# Dover_Driver.net
KiCad netlist of a schematic drawn in EAGLE
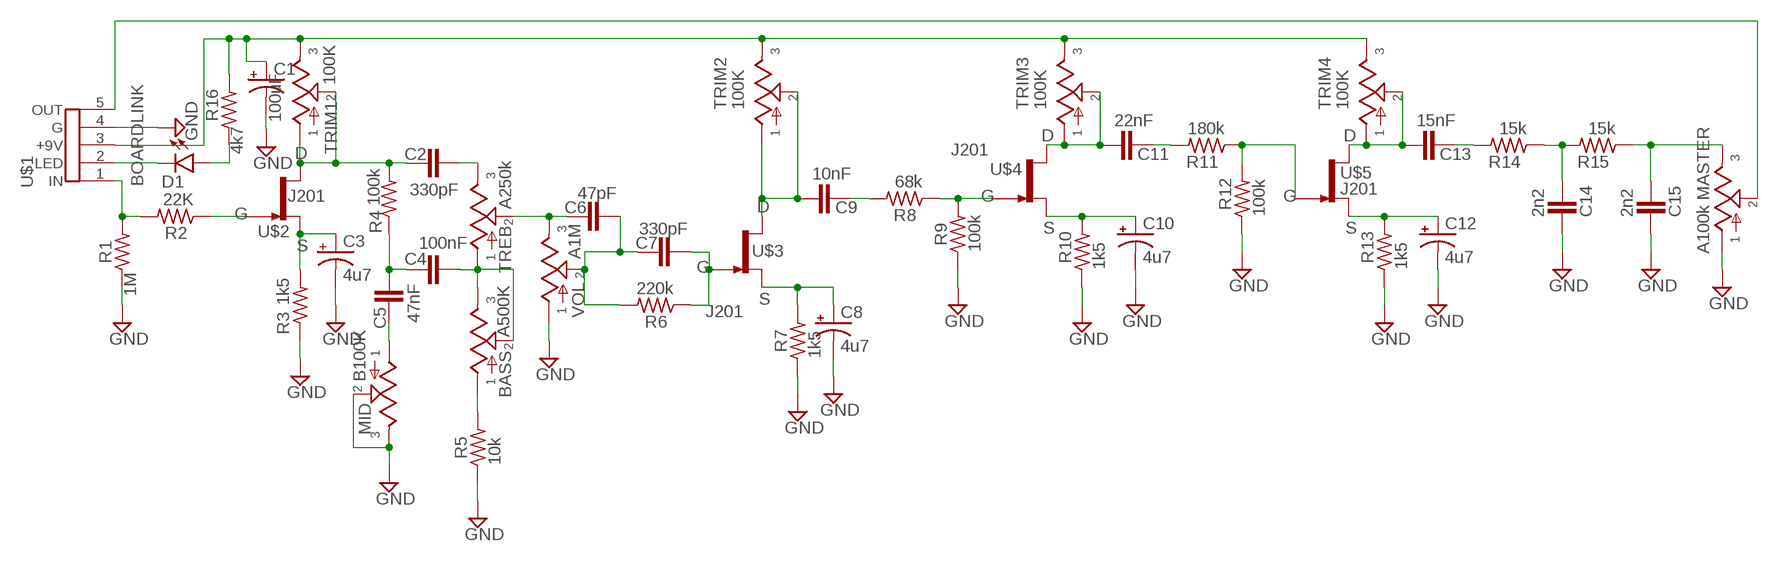
[diagram p0: schematic, sheet 1]

(export (version "E")
  (design (tool "Eeschema 10.0.6"))
  (components
    (comp (ref "BASS")
      (value "A500K")
      (footprint "eagle-import:16MM")
      (libsource (lib "eagle-import") (part "POT16MM"))
    )
    (comp (ref "C1")
      (value "100uF")
      (footprint "eagle-import:063_025")
      (libsource (lib "eagle-import") (part "0631"))
    )
    (comp (ref "C2")
      (value "330pF")
      (footprint "eagle-import:050X030_025")
      (libsource (lib "eagle-import") (part "050X030_0251"))
    )
    (comp (ref "C3")
      (value "4u7")
      (footprint "eagle-import:050_020_1")
      (libsource (lib "eagle-import") (part "0501"))
    )
    (comp (ref "C4")
      (value "100nF")
      (footprint "eagle-import:075X040")
      (libsource (lib "eagle-import") (part "075X0402"))
    )
    (comp (ref "C5")
      (value "47nF")
      (footprint "eagle-import:072X025")
      (libsource (lib "eagle-import") (part "072X0252"))
    )
    (comp (ref "C6")
      (value "47pF")
      (footprint "eagle-import:050X030_025")
      (libsource (lib "eagle-import") (part "050X030_0251"))
    )
    (comp (ref "C7")
      (value "330pF")
      (footprint "eagle-import:050X030_025")
      (libsource (lib "eagle-import") (part "050X030_0251"))
    )
    (comp (ref "C8")
      (value "4u7")
      (footprint "eagle-import:050_020_1")
      (libsource (lib "eagle-import") (part "0501"))
    )
    (comp (ref "C9")
      (value "10nF")
      (footprint "eagle-import:072X025")
      (libsource (lib "eagle-import") (part "072X0252"))
    )
    (comp (ref "C10")
      (value "4u7")
      (footprint "eagle-import:050_020_1")
      (libsource (lib "eagle-import") (part "0501"))
    )
    (comp (ref "C11")
      (value "22nF")
      (footprint "eagle-import:072X025")
      (libsource (lib "eagle-import") (part "072X0252"))
    )
    (comp (ref "C12")
      (value "4u7")
      (footprint "eagle-import:050_020_1")
      (libsource (lib "eagle-import") (part "0501"))
    )
    (comp (ref "C13")
      (value "15nF")
      (footprint "eagle-import:072X025")
      (libsource (lib "eagle-import") (part "072X0252"))
    )
    (comp (ref "C14")
      (value "2n2")
      (footprint "eagle-import:072X025")
      (libsource (lib "eagle-import") (part "072X0252"))
    )
    (comp (ref "C15")
      (value "2n2")
      (footprint "eagle-import:072X025")
      (libsource (lib "eagle-import") (part "072X0252"))
    )
    (comp (ref "D1")
      (value "LED3MM")
      (footprint "eagle-import:LED3MM")
      (libsource (lib "eagle-import") (part "LED3MM"))
    )
    (comp (ref "MASTER")
      (value "A100k")
      (footprint "eagle-import:16MM")
      (libsource (lib "eagle-import") (part "POT16MM"))
    )
    (comp (ref "MID")
      (value "B100K")
      (footprint "eagle-import:16MM")
      (libsource (lib "eagle-import") (part "POT16MM"))
    )
    (comp (ref "R1")
      (value "1M")
      (footprint "eagle-import:R0207_3")
      (libsource (lib "eagle-import") (part "6MM.3"))
    )
    (comp (ref "R2")
      (value "22K")
      (footprint "eagle-import:R0207_3")
      (libsource (lib "eagle-import") (part "6MM.3"))
    )
    (comp (ref "R3")
      (value "1k5")
      (footprint "eagle-import:R0207_3")
      (libsource (lib "eagle-import") (part "6MM.3"))
    )
    (comp (ref "R4")
      (value "100k")
      (footprint "eagle-import:R0207_3")
      (libsource (lib "eagle-import") (part "6MM.3"))
    )
    (comp (ref "R5")
      (value "10k")
      (footprint "eagle-import:R0207_3")
      (libsource (lib "eagle-import") (part "6MM.3"))
    )
    (comp (ref "R6")
      (value "220k")
      (footprint "eagle-import:R0207_3")
      (libsource (lib "eagle-import") (part "6MM.3"))
    )
    (comp (ref "R7")
      (value "1k5")
      (footprint "eagle-import:R0207_3")
      (libsource (lib "eagle-import") (part "6MM.3"))
    )
    (comp (ref "R8")
      (value "68k")
      (footprint "eagle-import:R0207_3")
      (libsource (lib "eagle-import") (part "6MM.3"))
    )
    (comp (ref "R9")
      (value "100k")
      (footprint "eagle-import:R0207_3")
      (libsource (lib "eagle-import") (part "6MM.3"))
    )
    (comp (ref "R10")
      (value "1k5")
      (footprint "eagle-import:R0207_3")
      (libsource (lib "eagle-import") (part "6MM.3"))
    )
    (comp (ref "R11")
      (value "180k")
      (footprint "eagle-import:R0207_3")
      (libsource (lib "eagle-import") (part "6MM.3"))
    )
    (comp (ref "R12")
      (value "100k")
      (footprint "eagle-import:R0207_3")
      (libsource (lib "eagle-import") (part "6MM.3"))
    )
    (comp (ref "R13")
      (value "1k5")
      (footprint "eagle-import:R0207_3")
      (libsource (lib "eagle-import") (part "6MM.3"))
    )
    (comp (ref "R14")
      (value "15k")
      (footprint "eagle-import:R0207_3")
      (libsource (lib "eagle-import") (part "6MM.3"))
    )
    (comp (ref "R15")
      (value "15k")
      (footprint "eagle-import:R0207_3")
      (libsource (lib "eagle-import") (part "6MM.3"))
    )
    (comp (ref "R16")
      (value "4k7")
      (footprint "eagle-import:R0207_3")
      (libsource (lib "eagle-import") (part "6MM.3"))
    )
    (comp (ref "TREB")
      (value "A250k")
      (footprint "eagle-import:16MM")
      (libsource (lib "eagle-import") (part "POT16MM"))
    )
    (comp (ref "TRIM1")
      (value "100K")
      (footprint "eagle-import:ROUNDTRIM")
      (libsource (lib "eagle-import") (part "xc_library_POTTRIM"))
    )
    (comp (ref "TRIM2")
      (value "100K")
      (footprint "eagle-import:ROUNDTRIM")
      (libsource (lib "eagle-import") (part "xc_library_POTTRIM"))
    )
    (comp (ref "TRIM3")
      (value "100K")
      (footprint "eagle-import:ROUNDTRIM")
      (libsource (lib "eagle-import") (part "xc_library_POTTRIM"))
    )
    (comp (ref "TRIM4")
      (value "100K")
      (footprint "eagle-import:ROUNDTRIM")
      (libsource (lib "eagle-import") (part "xc_library_POTTRIM"))
    )
    (comp (ref "U$1")
      (value "BOARDLINK")
      (footprint "eagle-import:BOARDLINK")
      (libsource (lib "eagle-import") (part "BOARDLINK"))
    )
    (comp (ref "U$2")
      (value "J201")
      (footprint "eagle-import:SOT23")
      (libsource (lib "eagle-import") (part "MMBF5458"))
    )
    (comp (ref "U$3")
      (value "J201")
      (footprint "eagle-import:SOT23")
      (libsource (lib "eagle-import") (part "MMBF5458"))
    )
    (comp (ref "U$4")
      (value "J201")
      (footprint "eagle-import:SOT23")
      (libsource (lib "eagle-import") (part "MMBF5458"))
    )
    (comp (ref "U$5")
      (value "J201")
      (footprint "eagle-import:SOT23")
      (libsource (lib "eagle-import") (part "MMBF5458"))
    )
    (comp (ref "VOL")
      (value "A1M")
      (footprint "eagle-import:16MM")
      (libsource (lib "eagle-import") (part "POT16MM"))
    )
  )
  (nets
    (net (code "1") (name "GND") (class "Default")
      (node (ref "C1") (pin "-") (pinfunction "-_-") (pintype "passive"))
      (node (ref "C10") (pin "-") (pinfunction "-_-") (pintype "passive"))
      (node (ref "C12") (pin "-") (pinfunction "-_-") (pintype "passive"))
      (node (ref "C14") (pin "2") (pinfunction "2_2") (pintype "passive"))
      (node (ref "C15") (pin "2") (pinfunction "2_2") (pintype "passive"))
      (node (ref "C3") (pin "-") (pinfunction "-_-") (pintype "passive"))
      (node (ref "C8") (pin "-") (pinfunction "-_-") (pintype "passive"))
      (node (ref "MASTER") (pin "1") (pinfunction "1_1") (pintype "passive"))
      (node (ref "MID") (pin "2") (pinfunction "2_2") (pintype "passive"))
      (node (ref "MID") (pin "3") (pinfunction "3_3") (pintype "passive"))
      (node (ref "R1") (pin "1") (pinfunction "1_1") (pintype "passive"))
      (node (ref "R10") (pin "1") (pinfunction "1_1") (pintype "passive"))
      (node (ref "R12") (pin "1") (pinfunction "1_1") (pintype "passive"))
      (node (ref "R13") (pin "1") (pinfunction "1_1") (pintype "passive"))
      (node (ref "R3") (pin "1") (pinfunction "1_1") (pintype "passive"))
      (node (ref "R5") (pin "1") (pinfunction "1_1") (pintype "passive"))
      (node (ref "R7") (pin "1") (pinfunction "1_1") (pintype "passive"))
      (node (ref "R9") (pin "1") (pinfunction "1_1") (pintype "passive"))
      (node (ref "U$1") (pin "4") (pinfunction "G_4") (pintype "bidirectional"))
      (node (ref "VOL") (pin "1") (pinfunction "1_1") (pintype "passive"))
    )
    (net (code "2") (name "Net-(BASS-Pad1)") (class "Default")
      (node (ref "BASS") (pin "1") (pinfunction "1_1") (pintype "passive"))
      (node (ref "R5") (pin "2") (pinfunction "2_2") (pintype "passive"))
    )
    (net (code "3") (name "Net-(BASS-Pad2)") (class "Default")
      (node (ref "BASS") (pin "2") (pinfunction "2_2") (pintype "passive"))
      (node (ref "BASS") (pin "3") (pinfunction "3_3") (pintype "passive"))
      (node (ref "C4") (pin "2") (pinfunction "2_2") (pintype "passive"))
      (node (ref "TREB") (pin "1") (pinfunction "1_1") (pintype "passive"))
    )
    (net (code "4") (name "Net-(C2-Pad2)") (class "Default")
      (node (ref "C2") (pin "2") (pinfunction "2_2") (pintype "passive"))
      (node (ref "TREB") (pin "3") (pinfunction "3_3") (pintype "passive"))
    )
    (net (code "5") (name "Net-(C4-Pad1)") (class "Default")
      (node (ref "C4") (pin "1") (pinfunction "1_1") (pintype "passive"))
      (node (ref "C5") (pin "2") (pinfunction "2_2") (pintype "passive"))
      (node (ref "R4") (pin "1") (pinfunction "1_1") (pintype "passive"))
    )
    (net (code "6") (name "Net-(C5-Pad1)") (class "Default")
      (node (ref "C5") (pin "1") (pinfunction "1_1") (pintype "passive"))
      (node (ref "MID") (pin "1") (pinfunction "1_1") (pintype "passive"))
    )
    (net (code "7") (name "Net-(C6-Pad1)") (class "Default")
      (node (ref "C6") (pin "1") (pinfunction "1_1") (pintype "passive"))
      (node (ref "TREB") (pin "2") (pinfunction "2_2") (pintype "passive"))
      (node (ref "VOL") (pin "3") (pinfunction "3_3") (pintype "passive"))
    )
    (net (code "8") (name "Net-(C6-Pad2)") (class "Default")
      (node (ref "C6") (pin "2") (pinfunction "2_2") (pintype "passive"))
      (node (ref "C7") (pin "1") (pinfunction "1_1") (pintype "passive"))
      (node (ref "R6") (pin "2") (pinfunction "2_2") (pintype "passive"))
      (node (ref "VOL") (pin "2") (pinfunction "2_2") (pintype "passive"))
    )
    (net (code "9") (name "Net-(C9-Pad1)") (class "Default")
      (node (ref "C9") (pin "1") (pinfunction "1_1") (pintype "passive"))
      (node (ref "R8") (pin "2") (pinfunction "2_2") (pintype "passive"))
    )
    (net (code "10") (name "Net-(C11-Pad1)") (class "Default")
      (node (ref "C11") (pin "1") (pinfunction "1_1") (pintype "passive"))
      (node (ref "R11") (pin "2") (pinfunction "2_2") (pintype "passive"))
    )
    (net (code "11") (name "Net-(C13-Pad1)") (class "Default")
      (node (ref "C13") (pin "1") (pinfunction "1_1") (pintype "passive"))
      (node (ref "R14") (pin "2") (pinfunction "2_2") (pintype "passive"))
    )
    (net (code "12") (name "Net-(C14-Pad1)") (class "Default")
      (node (ref "C14") (pin "1") (pinfunction "1_1") (pintype "passive"))
      (node (ref "R14") (pin "1") (pinfunction "1_1") (pintype "passive"))
      (node (ref "R15") (pin "2") (pinfunction "2_2") (pintype "passive"))
    )
    (net (code "13") (name "Net-(C15-Pad1)") (class "Default")
      (node (ref "C15") (pin "1") (pinfunction "1_1") (pintype "passive"))
      (node (ref "MASTER") (pin "3") (pinfunction "3_3") (pintype "passive"))
      (node (ref "R15") (pin "1") (pinfunction "1_1") (pintype "passive"))
    )
    (net (code "14") (name "Net-(D1-C)") (class "Default")
      (node (ref "D1") (pin "K") (pinfunction "C_K") (pintype "passive"))
      (node (ref "U$1") (pin "2") (pinfunction "LED_2") (pintype "bidirectional"))
    )
    (net (code "15") (name "Net-(D1-PadA)") (class "Default")
      (node (ref "D1") (pin "A") (pinfunction "A_A") (pintype "passive"))
      (node (ref "R16") (pin "1") (pinfunction "1_1") (pintype "passive"))
    )
    (net (code "16") (name "Net-(U$1-+9V)") (class "Default")
      (node (ref "C1") (pin "+") (pinfunction "+_+") (pintype "passive"))
      (node (ref "R16") (pin "2") (pinfunction "2_2") (pintype "passive"))
      (node (ref "TRIM1") (pin "3") (pinfunction "3_3") (pintype "passive"))
      (node (ref "TRIM2") (pin "3") (pinfunction "3_3") (pintype "passive"))
      (node (ref "TRIM3") (pin "3") (pinfunction "3_3") (pintype "passive"))
      (node (ref "TRIM4") (pin "3") (pinfunction "3_3") (pintype "passive"))
      (node (ref "U$1") (pin "3") (pinfunction "+9V_3") (pintype "bidirectional"))
    )
    (net (code "17") (name "Net-(U$1-IN)") (class "Default")
      (node (ref "R1") (pin "2") (pinfunction "2_2") (pintype "passive"))
      (node (ref "R2") (pin "2") (pinfunction "2_2") (pintype "passive"))
      (node (ref "U$1") (pin "1") (pinfunction "IN_1") (pintype "bidirectional"))
    )
    (net (code "18") (name "Net-(U$1-OUT)") (class "Default")
      (node (ref "MASTER") (pin "2") (pinfunction "2_2") (pintype "passive"))
      (node (ref "U$1") (pin "5") (pinfunction "OUT_5") (pintype "bidirectional"))
    )
    (net (code "19") (name "Net-(U$2-D)") (class "Default")
      (node (ref "C2") (pin "1") (pinfunction "1_1") (pintype "passive"))
      (node (ref "R4") (pin "2") (pinfunction "2_2") (pintype "passive"))
      (node (ref "TRIM1") (pin "1") (pinfunction "1_1") (pintype "passive"))
      (node (ref "TRIM1") (pin "2") (pinfunction "2_2") (pintype "passive"))
      (node (ref "U$2") (pin "1") (pinfunction "D_1") (pintype "passive"))
    )
    (net (code "20") (name "Net-(U$2-G)") (class "Default")
      (node (ref "R2") (pin "1") (pinfunction "1_1") (pintype "passive"))
      (node (ref "U$2") (pin "3") (pinfunction "G_3") (pintype "passive"))
    )
    (net (code "21") (name "Net-(U$2-S)") (class "Default")
      (node (ref "C3") (pin "+") (pinfunction "+_+") (pintype "passive"))
      (node (ref "R3") (pin "2") (pinfunction "2_2") (pintype "passive"))
      (node (ref "U$2") (pin "2") (pinfunction "S_2") (pintype "passive"))
    )
    (net (code "22") (name "Net-(U$3-D)") (class "Default")
      (node (ref "C9") (pin "2") (pinfunction "2_2") (pintype "passive"))
      (node (ref "TRIM2") (pin "1") (pinfunction "1_1") (pintype "passive"))
      (node (ref "TRIM2") (pin "2") (pinfunction "2_2") (pintype "passive"))
      (node (ref "U$3") (pin "1") (pinfunction "D_1") (pintype "passive"))
    )
    (net (code "23") (name "Net-(U$3-G)") (class "Default")
      (node (ref "C7") (pin "2") (pinfunction "2_2") (pintype "passive"))
      (node (ref "R6") (pin "1") (pinfunction "1_1") (pintype "passive"))
      (node (ref "U$3") (pin "3") (pinfunction "G_3") (pintype "passive"))
    )
    (net (code "24") (name "Net-(U$3-S)") (class "Default")
      (node (ref "C8") (pin "+") (pinfunction "+_+") (pintype "passive"))
      (node (ref "R7") (pin "2") (pinfunction "2_2") (pintype "passive"))
      (node (ref "U$3") (pin "2") (pinfunction "S_2") (pintype "passive"))
    )
    (net (code "25") (name "Net-(U$4-D)") (class "Default")
      (node (ref "C11") (pin "2") (pinfunction "2_2") (pintype "passive"))
      (node (ref "TRIM3") (pin "1") (pinfunction "1_1") (pintype "passive"))
      (node (ref "TRIM3") (pin "2") (pinfunction "2_2") (pintype "passive"))
      (node (ref "U$4") (pin "1") (pinfunction "D_1") (pintype "passive"))
    )
    (net (code "26") (name "Net-(U$4-G)") (class "Default")
      (node (ref "R8") (pin "1") (pinfunction "1_1") (pintype "passive"))
      (node (ref "R9") (pin "2") (pinfunction "2_2") (pintype "passive"))
      (node (ref "U$4") (pin "3") (pinfunction "G_3") (pintype "passive"))
    )
    (net (code "27") (name "Net-(U$4-S)") (class "Default")
      (node (ref "C10") (pin "+") (pinfunction "+_+") (pintype "passive"))
      (node (ref "R10") (pin "2") (pinfunction "2_2") (pintype "passive"))
      (node (ref "U$4") (pin "2") (pinfunction "S_2") (pintype "passive"))
    )
    (net (code "28") (name "Net-(U$5-D)") (class "Default")
      (node (ref "C13") (pin "2") (pinfunction "2_2") (pintype "passive"))
      (node (ref "TRIM4") (pin "1") (pinfunction "1_1") (pintype "passive"))
      (node (ref "TRIM4") (pin "2") (pinfunction "2_2") (pintype "passive"))
      (node (ref "U$5") (pin "1") (pinfunction "D_1") (pintype "passive"))
    )
    (net (code "29") (name "Net-(U$5-G)") (class "Default")
      (node (ref "R11") (pin "1") (pinfunction "1_1") (pintype "passive"))
      (node (ref "R12") (pin "2") (pinfunction "2_2") (pintype "passive"))
      (node (ref "U$5") (pin "3") (pinfunction "G_3") (pintype "passive"))
    )
    (net (code "30") (name "Net-(U$5-S)") (class "Default")
      (node (ref "C12") (pin "+") (pinfunction "+_+") (pintype "passive"))
      (node (ref "R13") (pin "2") (pinfunction "2_2") (pintype "passive"))
      (node (ref "U$5") (pin "2") (pinfunction "S_2") (pintype "passive"))
    )
  )
)
